# Encoders.net
KiCad netlist of a schematic drawn in Altium Designer
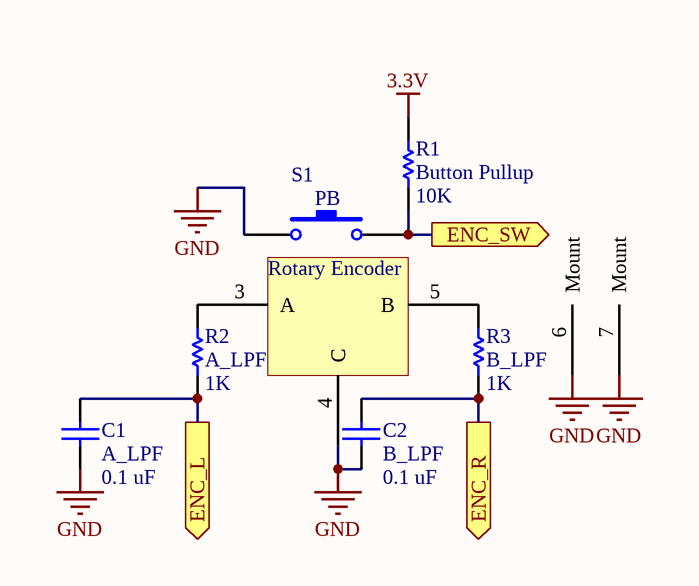
[diagram p0: Encoders.SchDoc]

(export (version "E")
  (design (tool "Eeschema 10.0.6"))
  (components
    (comp (ref "C1")
      (value "A_LPF")
      (footprint "C0805")
      (description "Capacitor")
      (fields (field (name "ALTIUM_VALUE") "0.1 uF") (field (name "PUBLISHER") "Altium Limited"))
      (libsource (lib "Miscellaneous Devices") (part "Cap"))
    )
    (comp (ref "C2")
      (value "B_LPF")
      (footprint "C0805")
      (description "Capacitor")
      (fields (field (name "ALTIUM_VALUE") "0.1 uF") (field (name "PUBLISHER") "Altium Limited"))
      (libsource (lib "Miscellaneous Devices") (part "Cap"))
    )
    (comp (ref "R1")
      (value "Button Pullup")
      (footprint "6-0805_N")
      (description "Resistor")
      (fields (field (name "ALTIUM_VALUE") "10K") (field (name "PUBLISHER") "Altium Limited"))
      (libsource (lib "Miscellaneous Devices") (part "Res1"))
    )
    (comp (ref "R2")
      (value "A_LPF")
      (footprint "6-0805_N")
      (description "Resistor")
      (fields (field (name "ALTIUM_VALUE") "1K") (field (name "PUBLISHER") "Altium Limited"))
      (libsource (lib "Miscellaneous Devices") (part "Res1"))
    )
    (comp (ref "R3")
      (value "B_LPF")
      (footprint "6-0805_N")
      (description "Resistor")
      (fields (field (name "ALTIUM_VALUE") "1K") (field (name "PUBLISHER") "Altium Limited"))
      (libsource (lib "Miscellaneous Devices") (part "Res1"))
    )
    (comp (ref "S1")
      (value "Rotary Encoder")
      (footprint "Rotary Encoder SF")
      (libsource (lib "FlexControl") (part "Rotary Encoder"))
    )
  )
  (nets
    (net (code "1") (name "/ENC_L") (class "Default")
      (node (ref "C1") (pin "2") (pinfunction "2_2") (pintype "passive"))
      (node (ref "R2") (pin "2") (pinfunction "2_2") (pintype "passive"))
    )
    (net (code "2") (name "/ENC_R") (class "Default")
      (node (ref "C2") (pin "2") (pinfunction "2_2") (pintype "passive"))
      (node (ref "R3") (pin "2") (pinfunction "2_2") (pintype "passive"))
    )
    (net (code "3") (name "/ENC_SW") (class "Default")
      (node (ref "R1") (pin "2") (pinfunction "2_2") (pintype "passive"))
      (node (ref "S1") (pin "2") (pinfunction "2_2") (pintype "passive"))
    )
    (net (code "4") (name "3.3V") (class "Default")
      (node (ref "R1") (pin "1") (pinfunction "1_1") (pintype "passive"))
    )
    (net (code "5") (name "GND") (class "Default")
      (node (ref "C1") (pin "1") (pinfunction "1_1") (pintype "passive"))
      (node (ref "C2") (pin "1") (pinfunction "1_1") (pintype "passive"))
      (node (ref "S1") (pin "1") (pinfunction "1_1") (pintype "passive"))
      (node (ref "S1") (pin "4") (pinfunction "C_4") (pintype "passive"))
      (node (ref "S1") (pin "6") (pinfunction "Mount_6") (pintype "passive"))
      (node (ref "S1") (pin "7") (pinfunction "Mount_7") (pintype "passive"))
    )
    (net (code "6") (name "Net-(S1-A)") (class "Default")
      (node (ref "R2") (pin "1") (pinfunction "1_1") (pintype "passive"))
      (node (ref "S1") (pin "3") (pinfunction "A_3") (pintype "passive"))
    )
    (net (code "7") (name "Net-(S1-B)") (class "Default")
      (node (ref "R3") (pin "1") (pinfunction "1_1") (pintype "passive"))
      (node (ref "S1") (pin "5") (pinfunction "B_5") (pintype "passive"))
    )
  )
)
